# mainboard.net
KiCad netlist of a schematic drawn in EAGLE
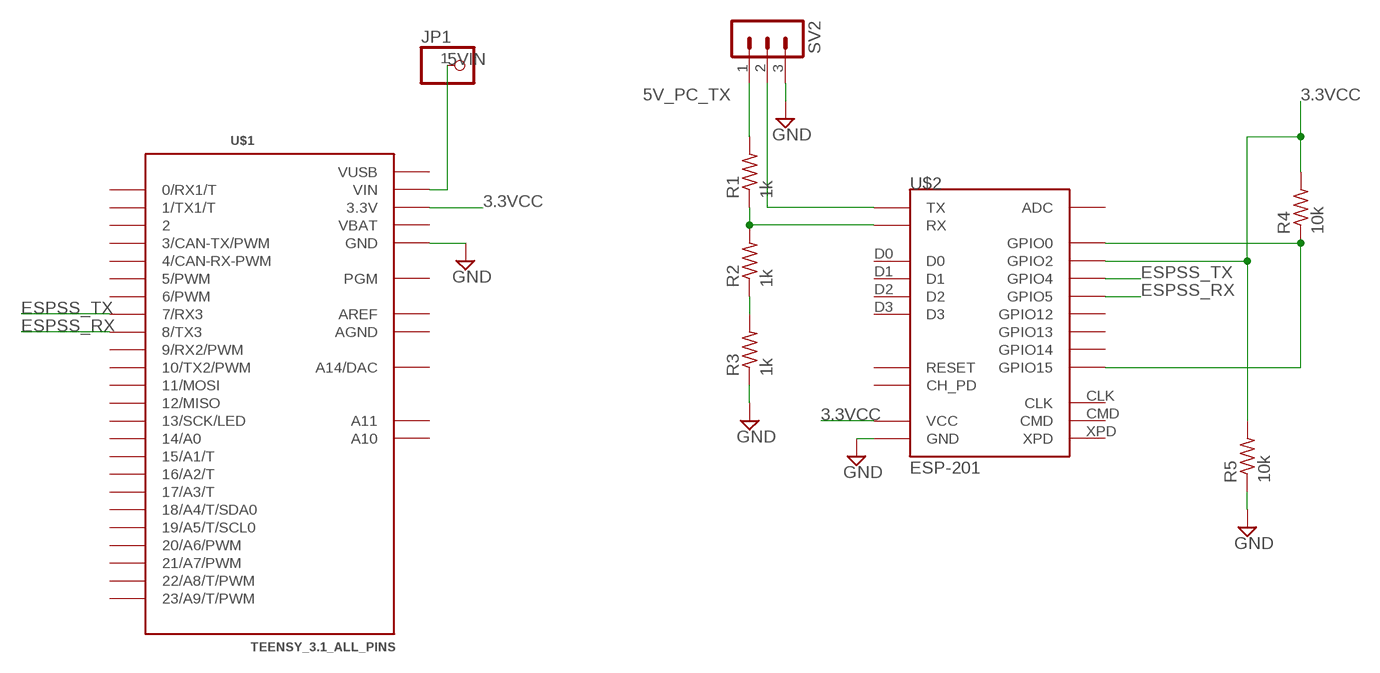
[diagram p0: schematic, sheet 1]

(export (version "E")
  (design (tool "Eeschema 10.0.6"))
  (components
    (comp (ref "JP1")
      (value "PINHD-1X1")
      (footprint "eagle-import:1X01")
      (libsource (lib "eagle-import") (part "PINHD-1X1"))
    )
    (comp (ref "R1")
      (value "1k")
      (footprint "eagle-import:0207_7")
      (libsource (lib "eagle-import") (part "R-US_0207/7"))
    )
    (comp (ref "R2")
      (value "1k")
      (footprint "eagle-import:0207_7")
      (libsource (lib "eagle-import") (part "R-US_0207/7"))
    )
    (comp (ref "R3")
      (value "1k")
      (footprint "eagle-import:0207_7")
      (libsource (lib "eagle-import") (part "R-US_0207/7"))
    )
    (comp (ref "R4")
      (value "10k")
      (footprint "eagle-import:0207_7")
      (libsource (lib "eagle-import") (part "R-US_0207/7"))
    )
    (comp (ref "R5")
      (value "10k")
      (footprint "eagle-import:0207_7")
      (libsource (lib "eagle-import") (part "R-US_0207/7"))
    )
    (comp (ref "SV2")
      (value "MA03-1")
      (footprint "eagle-import:MA03-1")
      (libsource (lib "eagle-import") (part "MA03-1"))
    )
    (comp (ref "U$1")
      (value "TEENSY_3.1_ALL_PINS")
      (footprint "eagle-import:TEENSY3-ALL_PINS")
      (libsource (lib "eagle-import") (part "TEENSY_3.1_ALL_PINS"))
    )
    (comp (ref "U$2")
      (value "ESP-201")
      (footprint "eagle-import:ESP-201")
      (libsource (lib "eagle-import") (part "ESP-201"))
    )
  )
  (nets
    (net (code "1") (name "/3.3VCC") (class "Default")
      (node (ref "R4") (pin "2") (pinfunction "2_2") (pintype "passive"))
      (node (ref "R5") (pin "2") (pinfunction "2_2") (pintype "passive"))
      (node (ref "U$1") (pin "3.3V") (pinfunction "3.3V_3.3V") (pintype "power_in"))
      (node (ref "U$1") (pin "3.3V1") (pinfunction "3.3V_3.3V1") (pintype "power_in"))
      (node (ref "U$2") (pin "3V3") (pinfunction "VCC_3V3") (pintype "bidirectional"))
      (node (ref "U$2") (pin "3V3_2") (pinfunction "VCC_3V3_2") (pintype "bidirectional"))
      (node (ref "U$2") (pin "3V3_3") (pinfunction "VCC_3V3_3") (pintype "bidirectional"))
      (node (ref "U$2") (pin "GPIO2") (pinfunction "GPIO2_GPIO2") (pintype "bidirectional"))
    )
    (net (code "2") (name "/5VIN") (class "Default")
      (node (ref "JP1") (pin "1") (pinfunction "1_1") (pintype "passive"))
      (node (ref "U$1") (pin "VIN") (pinfunction "VIN_VIN") (pintype "power_in"))
    )
    (net (code "3") (name "/5V_PC_TX") (class "Default")
      (node (ref "R1") (pin "2") (pinfunction "2_2") (pintype "passive"))
      (node (ref "SV2") (pin "1") (pinfunction "1_1") (pintype "passive"))
    )
    (net (code "4") (name "/AGND") (class "Default")
      (node (ref "U$1") (pin "AGND") (pinfunction "AGND_AGND") (pintype "power_in"))
    )
    (net (code "5") (name "/AREF") (class "Default")
      (node (ref "U$1") (pin "AREF") (pinfunction "AREF_AREF") (pintype "power_in"))
    )
    (net (code "6") (name "/ESPSS_RX") (class "Default")
      (node (ref "U$1") (pin "8") (pinfunction "8/TX3_8") (pintype "bidirectional"))
      (node (ref "U$2") (pin "GPIO5") (pinfunction "GPIO5_GPIO5") (pintype "bidirectional"))
    )
    (net (code "7") (name "/ESPSS_TX") (class "Default")
      (node (ref "U$1") (pin "7") (pinfunction "7/RX3_7") (pintype "bidirectional"))
      (node (ref "U$2") (pin "GPIO4") (pinfunction "GPIO4_GPIO4") (pintype "bidirectional"))
    )
    (net (code "8") (name "/VBAT") (class "Default")
      (node (ref "U$1") (pin "VBAT") (pinfunction "VBAT_VBAT") (pintype "power_in"))
    )
    (net (code "9") (name "/VUSB") (class "Default")
      (node (ref "U$1") (pin "VUSB") (pinfunction "VUSB_VUSB") (pintype "power_in"))
    )
    (net (code "10") (name "GND") (class "Default")
      (node (ref "R3") (pin "1") (pinfunction "1_1") (pintype "passive"))
      (node (ref "R5") (pin "1") (pinfunction "1_1") (pintype "passive"))
      (node (ref "SV2") (pin "3") (pinfunction "3_3") (pintype "passive"))
      (node (ref "U$1") (pin "GND") (pinfunction "GND_GND") (pintype "power_in"))
      (node (ref "U$1") (pin "GND1") (pinfunction "GND_GND1") (pintype "power_in"))
      (node (ref "U$2") (pin "GND") (pinfunction "GND_GND") (pintype "bidirectional"))
      (node (ref "U$2") (pin "GND_2") (pinfunction "GND_GND_2") (pintype "bidirectional"))
      (node (ref "U$2") (pin "GND_3") (pinfunction "GND_GND_3") (pintype "bidirectional"))
    )
    (net (code "11") (name "Net-(R1-Pad1)") (class "Default")
      (node (ref "R1") (pin "1") (pinfunction "1_1") (pintype "passive"))
      (node (ref "R2") (pin "2") (pinfunction "2_2") (pintype "passive"))
      (node (ref "U$2") (pin "RX") (pinfunction "RX_RX") (pintype "bidirectional"))
    )
    (net (code "12") (name "Net-(R2-Pad1)") (class "Default")
      (node (ref "R2") (pin "1") (pinfunction "1_1") (pintype "passive"))
      (node (ref "R3") (pin "2") (pinfunction "2_2") (pintype "passive"))
    )
    (net (code "13") (name "Net-(R4-Pad1)") (class "Default")
      (node (ref "R4") (pin "1") (pinfunction "1_1") (pintype "passive"))
      (node (ref "U$2") (pin "GPIO0") (pinfunction "GPIO0_GPIO0") (pintype "bidirectional"))
      (node (ref "U$2") (pin "GPIO15") (pinfunction "GPIO15_GPIO15") (pintype "bidirectional"))
    )
    (net (code "14") (name "Net-(SV2-Pad2)") (class "Default")
      (node (ref "SV2") (pin "2") (pinfunction "2_2") (pintype "passive"))
      (node (ref "U$2") (pin "TX") (pinfunction "TX_TX") (pintype "bidirectional"))
    )
    (net (code "15") (name "unconnected-(U$1-0{slash}RX1{slash}T-Pad0)") (class "Default")
      (node (ref "U$1") (pin "0") (pinfunction "0/RX1/T_0") (pintype "bidirectional"))
    )
    (net (code "16") (name "unconnected-(U$1-1{slash}TX1{slash}T-Pad1)") (class "Default")
      (node (ref "U$1") (pin "1") (pinfunction "1/TX1/T_1") (pintype "bidirectional"))
    )
    (net (code "17") (name "unconnected-(U$1-3{slash}CAN-TX{slash}PWM-Pad3)") (class "Default")
      (node (ref "U$1") (pin "3") (pinfunction "3/CAN-TX/PWM_3") (pintype "bidirectional"))
    )
    (net (code "18") (name "unconnected-(U$1-4{slash}CAN-RX-PWM-Pad4)") (class "Default")
      (node (ref "U$1") (pin "4") (pinfunction "4/CAN-RX-PWM_4") (pintype "bidirectional"))
    )
    (net (code "19") (name "unconnected-(U$1-5{slash}PWM-Pad5)") (class "Default")
      (node (ref "U$1") (pin "5") (pinfunction "5/PWM_5") (pintype "bidirectional"))
    )
    (net (code "20") (name "unconnected-(U$1-6{slash}PWM-Pad6)") (class "Default")
      (node (ref "U$1") (pin "6") (pinfunction "6/PWM_6") (pintype "bidirectional"))
    )
    (net (code "21") (name "unconnected-(U$1-9{slash}RX2{slash}PWM-Pad9)") (class "Default")
      (node (ref "U$1") (pin "9") (pinfunction "9/RX2/PWM_9") (pintype "bidirectional"))
    )
    (net (code "22") (name "unconnected-(U$1-10{slash}TX2{slash}PWM-Pad10)") (class "Default")
      (node (ref "U$1") (pin "10") (pinfunction "10/TX2/PWM_10") (pintype "bidirectional"))
    )
    (net (code "23") (name "unconnected-(U$1-11{slash}MOSI-Pad11)") (class "Default")
      (node (ref "U$1") (pin "11") (pinfunction "11/MOSI_11") (pintype "bidirectional"))
    )
    (net (code "24") (name "unconnected-(U$1-12{slash}MISO-Pad12)") (class "Default")
      (node (ref "U$1") (pin "12") (pinfunction "12/MISO_12") (pintype "bidirectional"))
    )
    (net (code "25") (name "unconnected-(U$1-13{slash}SCK{slash}LED-Pad13)") (class "Default")
      (node (ref "U$1") (pin "13") (pinfunction "13/SCK/LED_13") (pintype "bidirectional"))
    )
    (net (code "26") (name "unconnected-(U$1-15{slash}A1{slash}T-Pad15{slash}A1)") (class "Default")
      (node (ref "U$1") (pin "15/A1") (pinfunction "15/A1/T_15/A1") (pintype "bidirectional"))
    )
    (net (code "27") (name "unconnected-(U$1-16{slash}A2{slash}T-Pad16{slash}A2)") (class "Default")
      (node (ref "U$1") (pin "16/A2") (pinfunction "16/A2/T_16/A2") (pintype "bidirectional"))
    )
    (net (code "28") (name "unconnected-(U$1-17{slash}A3{slash}T-Pad17{slash}A3)") (class "Default")
      (node (ref "U$1") (pin "17/A3") (pinfunction "17/A3/T_17/A3") (pintype "bidirectional"))
    )
    (net (code "29") (name "unconnected-(U$1-18{slash}A4{slash}T{slash}SDA0-Pad18{slash}A4)") (class "Default")
      (node (ref "U$1") (pin "18/A4") (pinfunction "18/A4/T/SDA0_18/A4") (pintype "bidirectional"))
    )
    (net (code "30") (name "unconnected-(U$1-19{slash}A5{slash}T{slash}SCL0-Pad19{slash}A5)") (class "Default")
      (node (ref "U$1") (pin "19/A5") (pinfunction "19/A5/T/SCL0_19/A5") (pintype "bidirectional"))
    )
    (net (code "31") (name "unconnected-(U$1-20{slash}A6{slash}PWM-Pad20{slash}A6)") (class "Default")
      (node (ref "U$1") (pin "20/A6") (pinfunction "20/A6/PWM_20/A6") (pintype "bidirectional"))
    )
    (net (code "32") (name "unconnected-(U$1-21{slash}A7{slash}PWM-Pad21{slash}A7)") (class "Default")
      (node (ref "U$1") (pin "21/A7") (pinfunction "21/A7/PWM_21/A7") (pintype "bidirectional"))
    )
    (net (code "33") (name "unconnected-(U$1-22{slash}A8{slash}T{slash}PWM-Pad22{slash}A8)") (class "Default")
      (node (ref "U$1") (pin "22/A8") (pinfunction "22/A8/T/PWM_22/A8") (pintype "bidirectional"))
    )
    (net (code "34") (name "unconnected-(U$1-23{slash}A9{slash}T{slash}PWM-Pad23{slash}A9)") (class "Default")
      (node (ref "U$1") (pin "23/A9") (pinfunction "23/A9/T/PWM_23/A9") (pintype "bidirectional"))
    )
    (net (code "35") (name "unconnected-(U$1-A14{slash}DAC-PadRESET{slash}DAC)") (class "Default")
      (node (ref "U$1") (pin "RESET/DAC") (pinfunction "A14/DAC_RESET/DAC") (pintype "bidirectional"))
    )
    (net (code "36") (name "unconnected-(U$1-Pad2)") (class "Default")
      (node (ref "U$1") (pin "2") (pinfunction "2_2") (pintype "bidirectional"))
    )
    (net (code "37") (name "unconnected-(U$1-Pad14{slash}A0)") (class "Default")
      (node (ref "U$1") (pin "14/A0") (pinfunction "14/A0_14/A0") (pintype "bidirectional"))
    )
    (net (code "38") (name "unconnected-(U$1-PadA10)") (class "Default")
      (node (ref "U$1") (pin "A10") (pinfunction "A10_A10") (pintype "bidirectional"))
    )
    (net (code "39") (name "unconnected-(U$1-PadA11)") (class "Default")
      (node (ref "U$1") (pin "A11") (pinfunction "A11_A11") (pintype "bidirectional"))
    )
    (net (code "40") (name "unconnected-(U$1-PadPGM)") (class "Default")
      (node (ref "U$1") (pin "PGM") (pinfunction "PGM_PGM") (pintype "bidirectional"))
    )
    (net (code "41") (name "unconnected-(U$2-PadADC)") (class "Default")
      (node (ref "U$2") (pin "ADC") (pinfunction "ADC_ADC") (pintype "bidirectional"))
    )
    (net (code "42") (name "unconnected-(U$2-PadCH_PD)") (class "Default")
      (node (ref "U$2") (pin "CH_PD") (pinfunction "CH_PD_CH_PD") (pintype "bidirectional"))
    )
    (net (code "43") (name "unconnected-(U$2-PadCLK)") (class "Default")
      (node (ref "U$2") (pin "CLK") (pinfunction "CLK_CLK") (pintype "bidirectional"))
    )
    (net (code "44") (name "unconnected-(U$2-PadCMD)") (class "Default")
      (node (ref "U$2") (pin "CMD") (pinfunction "CMD_CMD") (pintype "bidirectional"))
    )
    (net (code "45") (name "unconnected-(U$2-PadD0)") (class "Default")
      (node (ref "U$2") (pin "D0") (pinfunction "D0_D0") (pintype "bidirectional"))
    )
    (net (code "46") (name "unconnected-(U$2-PadD1)") (class "Default")
      (node (ref "U$2") (pin "D1") (pinfunction "D1_D1") (pintype "bidirectional"))
    )
    (net (code "47") (name "unconnected-(U$2-PadD2)") (class "Default")
      (node (ref "U$2") (pin "D2") (pinfunction "D2_D2") (pintype "bidirectional"))
    )
    (net (code "48") (name "unconnected-(U$2-PadD3)") (class "Default")
      (node (ref "U$2") (pin "D3") (pinfunction "D3_D3") (pintype "bidirectional"))
    )
    (net (code "49") (name "unconnected-(U$2-PadGPIO12)") (class "Default")
      (node (ref "U$2") (pin "GPIO12") (pinfunction "GPIO12_GPIO12") (pintype "bidirectional"))
    )
    (net (code "50") (name "unconnected-(U$2-PadGPIO13)") (class "Default")
      (node (ref "U$2") (pin "GPIO13") (pinfunction "GPIO13_GPIO13") (pintype "bidirectional"))
    )
    (net (code "51") (name "unconnected-(U$2-PadGPIO14)") (class "Default")
      (node (ref "U$2") (pin "GPIO14") (pinfunction "GPIO14_GPIO14") (pintype "bidirectional"))
    )
    (net (code "52") (name "unconnected-(U$2-PadXPD)") (class "Default")
      (node (ref "U$2") (pin "XPD") (pinfunction "XPD_XPD") (pintype "bidirectional"))
    )
    (net (code "53") (name "unconnected-(U$2-RESET-PadRST)") (class "Default")
      (node (ref "U$2") (pin "RST") (pinfunction "RESET_RST") (pintype "bidirectional"))
    )
  )
)
